# Adafuit_9DOF.net
KiCad netlist of a schematic drawn in EAGLE
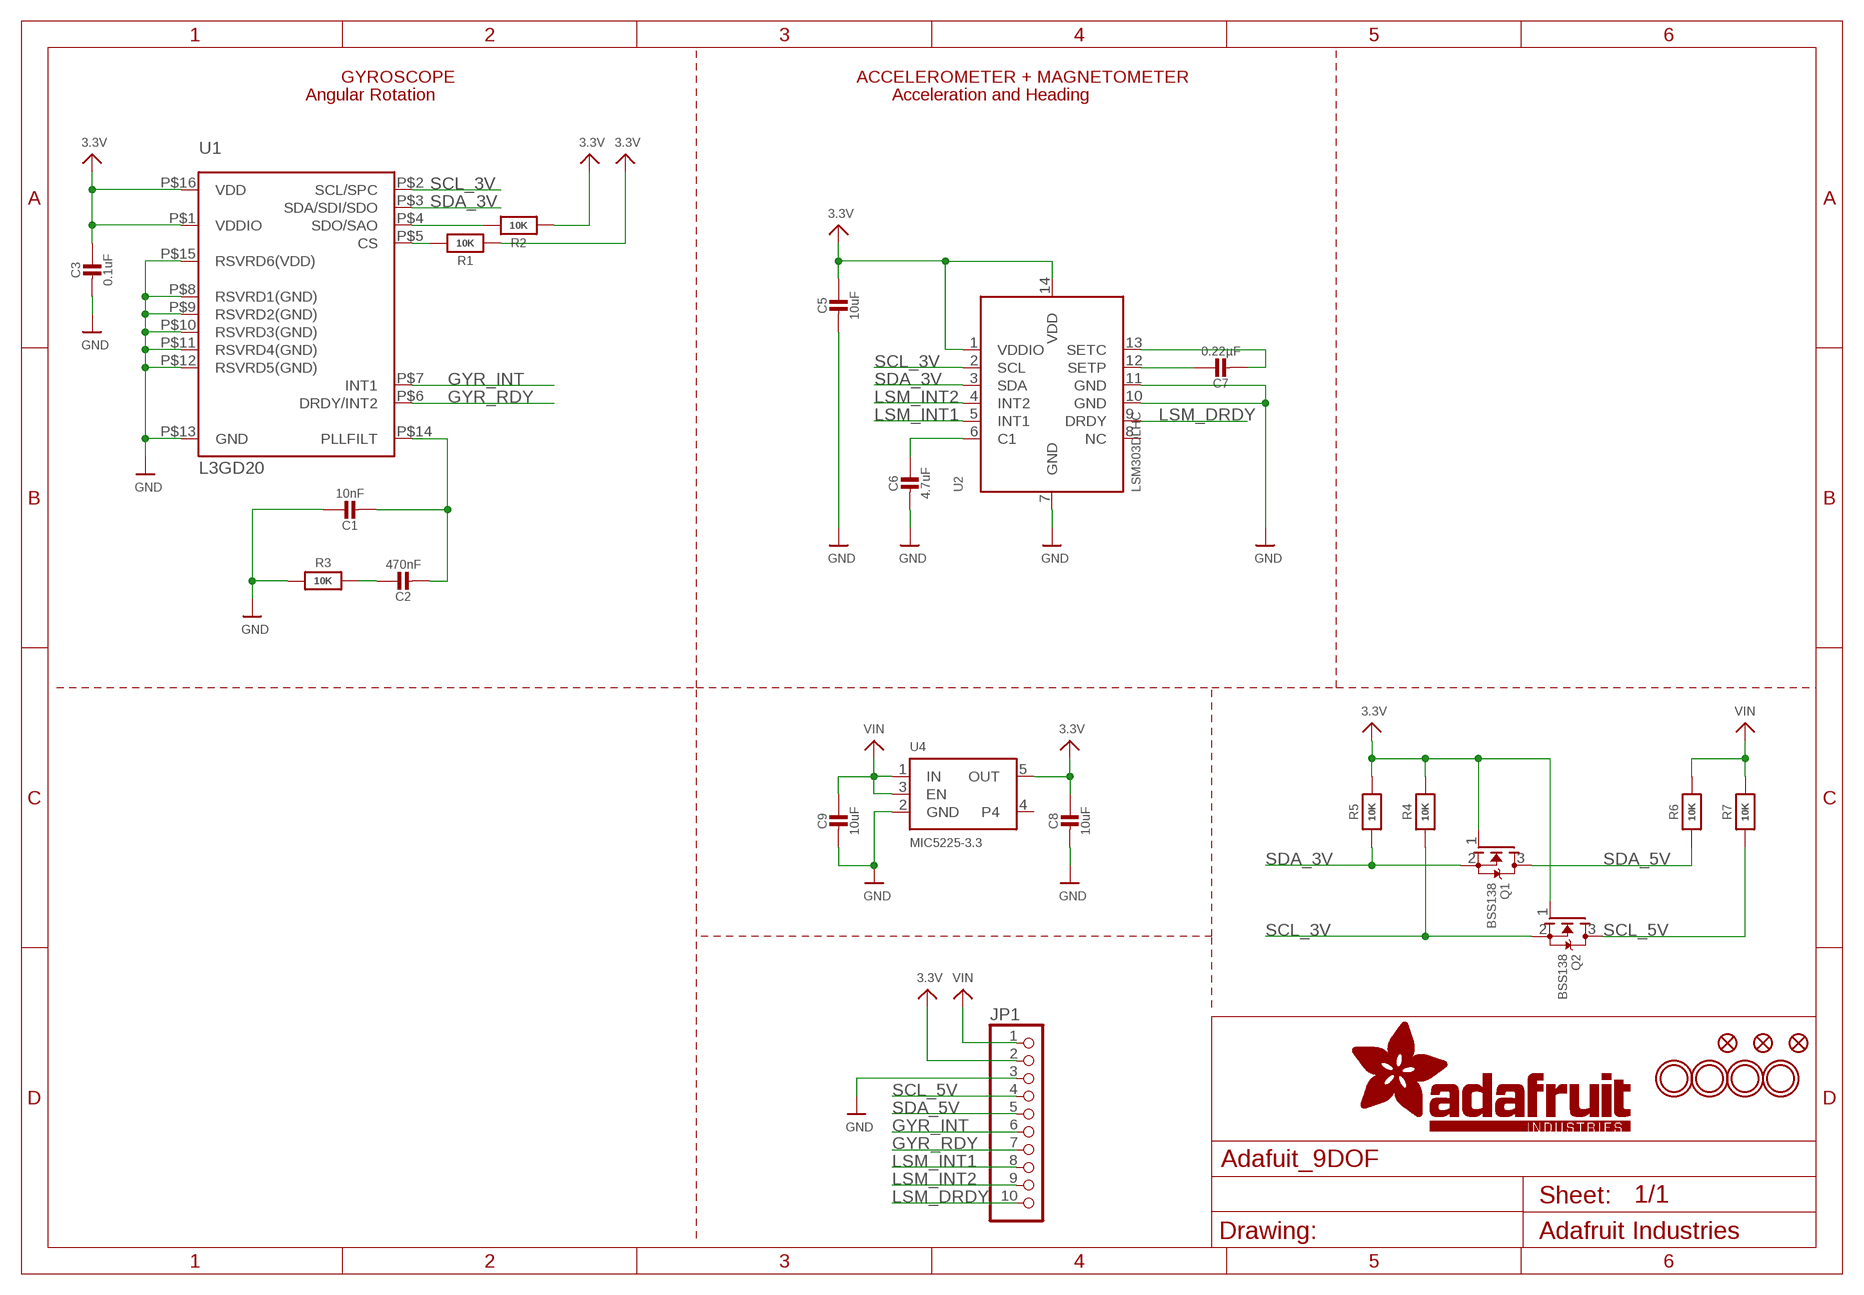
[diagram p0: schematic, sheet 1]

(export (version "E")
  (design (tool "Eeschema 10.0.6"))
  (components
    (comp (ref "C1")
      (value "10nF")
      (footprint "eagle-import:_0805MP")
      (libsource (lib "eagle-import") (part "CAP_CERAMIC_0805MP"))
    )
    (comp (ref "C2")
      (value "470nF")
      (footprint "eagle-import:_0805MP")
      (libsource (lib "eagle-import") (part "CAP_CERAMIC_0805MP"))
    )
    (comp (ref "C3")
      (value "0.1uF")
      (footprint "eagle-import:_0805MP")
      (libsource (lib "eagle-import") (part "CAP_CERAMIC_0805MP"))
    )
    (comp (ref "C5")
      (value "10uF")
      (footprint "eagle-import:_0805MP")
      (libsource (lib "eagle-import") (part "CAP_CERAMIC_0805MP"))
    )
    (comp (ref "C6")
      (value "4.7uF")
      (footprint "eagle-import:_0805MP")
      (libsource (lib "eagle-import") (part "CAP_CERAMIC_0805MP"))
    )
    (comp (ref "C7")
      (value "0.22µF")
      (footprint "eagle-import:_0805MP")
      (libsource (lib "eagle-import") (part "CAP_CERAMIC_0805MP"))
    )
    (comp (ref "C8")
      (value "10uF")
      (footprint "eagle-import:_0805MP")
      (libsource (lib "eagle-import") (part "CAP_CERAMIC_0805MP"))
    )
    (comp (ref "C9")
      (value "10uF")
      (footprint "eagle-import:_0805MP")
      (libsource (lib "eagle-import") (part "CAP_CERAMIC_0805MP"))
    )
    (comp (ref "FID1")
      (value "FIDUCIAL\"\"")
      (footprint "eagle-import:FIDUCIAL_1MM")
      (libsource (lib "eagle-import") (part "FIDUCIAL{dblquote}{dblquote}"))
    )
    (comp (ref "FID2")
      (value "FIDUCIAL\"\"")
      (footprint "eagle-import:FIDUCIAL_1MM")
      (libsource (lib "eagle-import") (part "FIDUCIAL{dblquote}{dblquote}"))
    )
    (comp (ref "FID3")
      (value "FIDUCIAL\"\"")
      (footprint "eagle-import:FIDUCIAL_1MM")
      (libsource (lib "eagle-import") (part "FIDUCIAL{dblquote}{dblquote}"))
    )
    (comp (ref "JP1")
      (value "HEADER-1X10ROUND")
      (footprint "eagle-import:1X10_ROUND")
      (libsource (lib "eagle-import") (part "HEADER-1X10ROUND"))
    )
    (comp (ref "Q1")
      (value "BSS138")
      (footprint "eagle-import:SOT23-WIDE")
      (libsource (lib "eagle-import") (part "MOSFET-NWIDE"))
    )
    (comp (ref "Q2")
      (value "BSS138")
      (footprint "eagle-import:SOT23-WIDE")
      (libsource (lib "eagle-import") (part "MOSFET-NWIDE"))
    )
    (comp (ref "R1")
      (value "10K")
      (footprint "eagle-import:_0805MP")
      (libsource (lib "eagle-import") (part "RESISTOR_0805MP"))
    )
    (comp (ref "R2")
      (value "10K")
      (footprint "eagle-import:_0805MP")
      (libsource (lib "eagle-import") (part "RESISTOR_0805MP"))
    )
    (comp (ref "R3")
      (value "10K")
      (footprint "eagle-import:_0805MP")
      (libsource (lib "eagle-import") (part "RESISTOR_0805MP"))
    )
    (comp (ref "R4")
      (value "10K")
      (footprint "eagle-import:_0805MP")
      (libsource (lib "eagle-import") (part "RESISTOR_0805MP"))
    )
    (comp (ref "R5")
      (value "10K")
      (footprint "eagle-import:_0805MP")
      (libsource (lib "eagle-import") (part "RESISTOR_0805MP"))
    )
    (comp (ref "R6")
      (value "10K")
      (footprint "eagle-import:_0805MP")
      (libsource (lib "eagle-import") (part "RESISTOR_0805MP"))
    )
    (comp (ref "R7")
      (value "10K")
      (footprint "eagle-import:_0805MP")
      (libsource (lib "eagle-import") (part "RESISTOR_0805MP"))
    )
    (comp (ref "U$28")
      (value "MOUNTINGHOLE2.5_THICK")
      (footprint "eagle-import:MOUNTINGHOLE_2.5_PLATED_THICK")
      (libsource (lib "eagle-import") (part "MOUNTINGHOLE2.5_THICK"))
    )
    (comp (ref "U$29")
      (value "MOUNTINGHOLE2.5_THICK")
      (footprint "eagle-import:MOUNTINGHOLE_2.5_PLATED_THICK")
      (libsource (lib "eagle-import") (part "MOUNTINGHOLE2.5_THICK"))
    )
    (comp (ref "U$30")
      (value "MOUNTINGHOLE2.5_THICK")
      (footprint "eagle-import:MOUNTINGHOLE_2.5_PLATED_THICK")
      (libsource (lib "eagle-import") (part "MOUNTINGHOLE2.5_THICK"))
    )
    (comp (ref "U$31")
      (value "MOUNTINGHOLE2.5_THICK")
      (footprint "eagle-import:MOUNTINGHOLE_2.5_PLATED_THICK")
      (libsource (lib "eagle-import") (part "MOUNTINGHOLE2.5_THICK"))
    )
    (comp (ref "U1")
      (value "L3GD20")
      (footprint "eagle-import:L3G4200D_LGA16L")
      (libsource (lib "eagle-import") (part "GYRO_L3G2400D"))
    )
    (comp (ref "U2")
      (value "LSM303DLHC")
      (footprint "eagle-import:LGA14")
      (libsource (lib "eagle-import") (part "LSM303DLHC"))
    )
    (comp (ref "U4")
      (value "MIC5225-3.3")
      (footprint "eagle-import:SOT23-5")
      (libsource (lib "eagle-import") (part "VREG_SOT23-5"))
    )
  )
  (nets
    (net (code "1") (name "/GYR_INT") (class "Default")
      (node (ref "JP1") (pin "6") (pinfunction "6_6") (pintype "passive"))
      (node (ref "U1") (pin "P$7") (pinfunction "INT1_P$7") (pintype "bidirectional"))
    )
    (net (code "2") (name "/GYR_RDY") (class "Default")
      (node (ref "JP1") (pin "7") (pinfunction "7_7") (pintype "passive"))
      (node (ref "U1") (pin "P$6") (pinfunction "DRDY/INT2_P$6") (pintype "bidirectional"))
    )
    (net (code "3") (name "/LSM_DRDY") (class "Default")
      (node (ref "JP1") (pin "10") (pinfunction "10_10") (pintype "passive"))
      (node (ref "U2") (pin "9") (pinfunction "DRDY_9") (pintype "output"))
    )
    (net (code "4") (name "/LSM_INT1") (class "Default")
      (node (ref "JP1") (pin "8") (pinfunction "8_8") (pintype "passive"))
      (node (ref "U2") (pin "5") (pinfunction "INT1_5") (pintype "output"))
    )
    (net (code "5") (name "/LSM_INT2") (class "Default")
      (node (ref "JP1") (pin "9") (pinfunction "9_9") (pintype "passive"))
      (node (ref "U2") (pin "4") (pinfunction "INT2_4") (pintype "output"))
    )
    (net (code "6") (name "/SCL_3V") (class "Default")
      (node (ref "Q2") (pin "2") (pinfunction "S_2") (pintype "bidirectional"))
      (node (ref "R4") (pin "1") (pinfunction "1_1") (pintype "passive"))
      (node (ref "U1") (pin "P$2") (pinfunction "SCL/SPC_P$2") (pintype "bidirectional"))
      (node (ref "U2") (pin "2") (pinfunction "SCL_2") (pintype "bidirectional"))
    )
    (net (code "7") (name "/SCL_5V") (class "Default")
      (node (ref "JP1") (pin "4") (pinfunction "4_4") (pintype "passive"))
      (node (ref "Q2") (pin "3") (pinfunction "D_3") (pintype "bidirectional"))
      (node (ref "R7") (pin "1") (pinfunction "1_1") (pintype "passive"))
    )
    (net (code "8") (name "/SDA_3V") (class "Default")
      (node (ref "Q1") (pin "2") (pinfunction "S_2") (pintype "bidirectional"))
      (node (ref "R5") (pin "1") (pinfunction "1_1") (pintype "passive"))
      (node (ref "U1") (pin "P$3") (pinfunction "SDA/SDI/SDO_P$3") (pintype "bidirectional"))
      (node (ref "U2") (pin "3") (pinfunction "SDA_3") (pintype "bidirectional"))
    )
    (net (code "9") (name "/SDA_5V") (class "Default")
      (node (ref "JP1") (pin "5") (pinfunction "5_5") (pintype "passive"))
      (node (ref "Q1") (pin "3") (pinfunction "D_3") (pintype "bidirectional"))
      (node (ref "R6") (pin "1") (pinfunction "1_1") (pintype "passive"))
    )
    (net (code "10") (name "3.3V") (class "Default")
      (node (ref "C3") (pin "1") (pinfunction "1_1") (pintype "passive"))
      (node (ref "C5") (pin "1") (pinfunction "1_1") (pintype "passive"))
      (node (ref "C8") (pin "1") (pinfunction "1_1") (pintype "passive"))
      (node (ref "JP1") (pin "2") (pinfunction "2_2") (pintype "passive"))
      (node (ref "Q1") (pin "1") (pinfunction "G_1") (pintype "bidirectional"))
      (node (ref "Q2") (pin "1") (pinfunction "G_1") (pintype "bidirectional"))
      (node (ref "R1") (pin "1") (pinfunction "1_1") (pintype "passive"))
      (node (ref "R2") (pin "1") (pinfunction "1_1") (pintype "passive"))
      (node (ref "R4") (pin "2") (pinfunction "2_2") (pintype "passive"))
      (node (ref "R5") (pin "2") (pinfunction "2_2") (pintype "passive"))
      (node (ref "U1") (pin "P$1") (pinfunction "VDDIO_P$1") (pintype "power_in"))
      (node (ref "U1") (pin "P$16") (pinfunction "VDD_P$16") (pintype "bidirectional"))
      (node (ref "U2") (pin "1") (pinfunction "VDDIO_1") (pintype "power_in"))
      (node (ref "U2") (pin "14") (pinfunction "VDD_14") (pintype "power_in"))
      (node (ref "U4") (pin "5") (pinfunction "OUT_5") (pintype "power_in"))
    )
    (net (code "11") (name "GND") (class "Default")
      (node (ref "C1") (pin "1") (pinfunction "1_1") (pintype "passive"))
      (node (ref "C3") (pin "2") (pinfunction "2_2") (pintype "passive"))
      (node (ref "C5") (pin "2") (pinfunction "2_2") (pintype "passive"))
      (node (ref "C6") (pin "2") (pinfunction "2_2") (pintype "passive"))
      (node (ref "C8") (pin "2") (pinfunction "2_2") (pintype "passive"))
      (node (ref "C9") (pin "2") (pinfunction "2_2") (pintype "passive"))
      (node (ref "JP1") (pin "3") (pinfunction "3_3") (pintype "passive"))
      (node (ref "R3") (pin "1") (pinfunction "1_1") (pintype "passive"))
      (node (ref "U1") (pin "P$10") (pinfunction "RSVRD3(GND)_P$10") (pintype "bidirectional"))
      (node (ref "U1") (pin "P$11") (pinfunction "RSVRD4(GND)_P$11") (pintype "bidirectional"))
      (node (ref "U1") (pin "P$12") (pinfunction "RSVRD5(GND)_P$12") (pintype "bidirectional"))
      (node (ref "U1") (pin "P$13") (pinfunction "GND_P$13") (pintype "bidirectional"))
      (node (ref "U1") (pin "P$15") (pinfunction "RSVRD6(VDD)_P$15") (pintype "bidirectional"))
      (node (ref "U1") (pin "P$8") (pinfunction "RSVRD1(GND)_P$8") (pintype "bidirectional"))
      (node (ref "U1") (pin "P$9") (pinfunction "RSVRD2(GND)_P$9") (pintype "bidirectional"))
      (node (ref "U2") (pin "10") (pinfunction "GND_10") (pintype "power_in"))
      (node (ref "U2") (pin "11") (pinfunction "GND_11") (pintype "power_in"))
      (node (ref "U2") (pin "7") (pinfunction "GND_7") (pintype "power_in"))
      (node (ref "U4") (pin "2") (pinfunction "GND_2") (pintype "power_in"))
    )
    (net (code "12") (name "Net-(C2-Pad1)") (class "Default")
      (node (ref "C2") (pin "1") (pinfunction "1_1") (pintype "passive"))
      (node (ref "R3") (pin "2") (pinfunction "2_2") (pintype "passive"))
    )
    (net (code "13") (name "Net-(U1-CS)") (class "Default")
      (node (ref "R1") (pin "2") (pinfunction "2_2") (pintype "passive"))
      (node (ref "U1") (pin "P$5") (pinfunction "CS_P$5") (pintype "bidirectional"))
    )
    (net (code "14") (name "Net-(U1-PLLFILT)") (class "Default")
      (node (ref "C1") (pin "2") (pinfunction "2_2") (pintype "passive"))
      (node (ref "C2") (pin "2") (pinfunction "2_2") (pintype "passive"))
      (node (ref "U1") (pin "P$14") (pinfunction "PLLFILT_P$14") (pintype "bidirectional"))
    )
    (net (code "15") (name "Net-(U1-SDO{slash}SAO)") (class "Default")
      (node (ref "R2") (pin "2") (pinfunction "2_2") (pintype "passive"))
      (node (ref "U1") (pin "P$4") (pinfunction "SDO/SAO_P$4") (pintype "bidirectional"))
    )
    (net (code "16") (name "Net-(U2-C1)") (class "Default")
      (node (ref "C6") (pin "1") (pinfunction "1_1") (pintype "passive"))
      (node (ref "U2") (pin "6") (pinfunction "C1_6") (pintype "bidirectional"))
    )
    (net (code "17") (name "Net-(U2-SETC)") (class "Default")
      (node (ref "C7") (pin "2") (pinfunction "2_2") (pintype "passive"))
      (node (ref "U2") (pin "13") (pinfunction "SETC_13") (pintype "bidirectional"))
    )
    (net (code "18") (name "Net-(U2-SETP)") (class "Default")
      (node (ref "C7") (pin "1") (pinfunction "1_1") (pintype "passive"))
      (node (ref "U2") (pin "12") (pinfunction "SETP_12") (pintype "bidirectional"))
    )
    (net (code "19") (name "VIN") (class "Default")
      (node (ref "C9") (pin "1") (pinfunction "1_1") (pintype "passive"))
      (node (ref "JP1") (pin "1") (pinfunction "1_1") (pintype "passive"))
      (node (ref "R6") (pin "2") (pinfunction "2_2") (pintype "passive"))
      (node (ref "R7") (pin "2") (pinfunction "2_2") (pintype "passive"))
      (node (ref "U4") (pin "1") (pinfunction "IN_1") (pintype "power_in"))
      (node (ref "U4") (pin "3") (pinfunction "EN_3") (pintype "input"))
    )
    (net (code "20") (name "unconnected-(U2-NC-Pad8)") (class "Default")
      (node (ref "U2") (pin "8") (pinfunction "NC_8") (pintype "bidirectional"))
    )
    (net (code "21") (name "unconnected-(U4-P4-Pad4)") (class "Default")
      (node (ref "U4") (pin "4") (pinfunction "P4_4") (pintype "bidirectional"))
    )
  )
)
